# load-cell.net
KiCad netlist of a schematic drawn in EAGLE
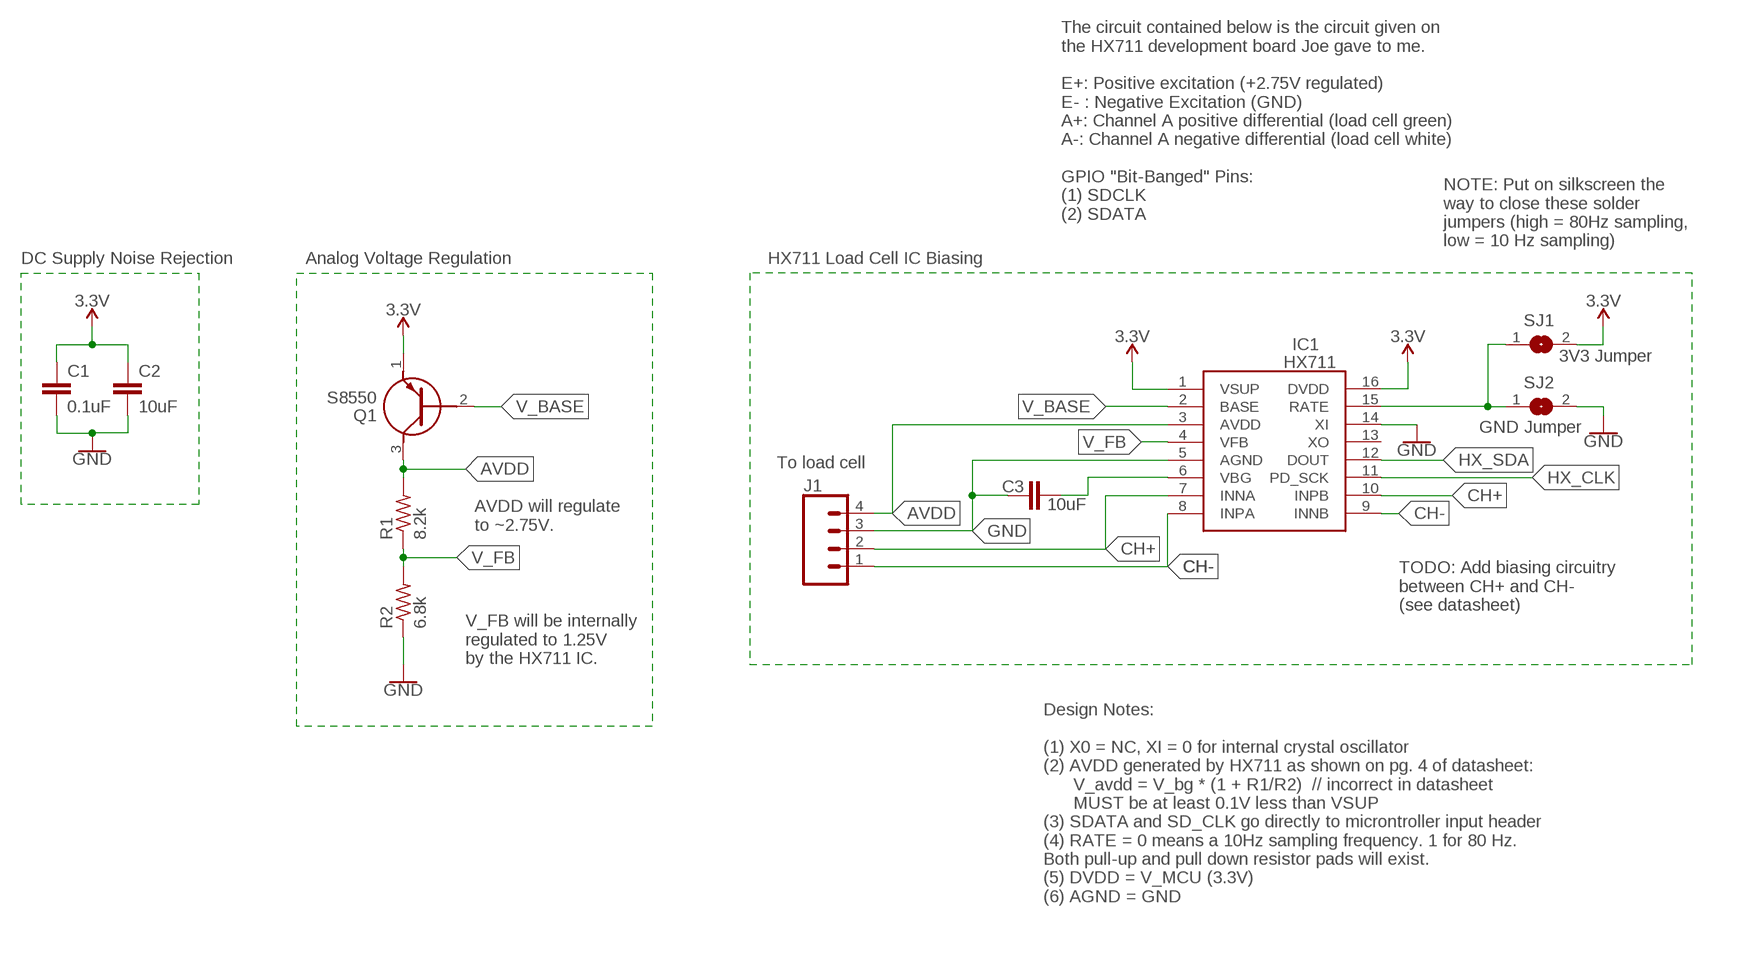
[diagram p0: schematic, sheet 1]

(export (version "E")
  (design (tool "Eeschema 10.0.6"))
  (components
    (comp (ref "C1")
      (value "0.1uF")
      (footprint "eagle-import:C0603")
      (libsource (lib "eagle-import") (part "CAPACITOR0603"))
    )
    (comp (ref "C2")
      (value "10uF")
      (footprint "eagle-import:C0603")
      (libsource (lib "eagle-import") (part "CAPACITOR0603"))
    )
    (comp (ref "C3")
      (value "10uF")
      (footprint "eagle-import:C0603")
      (libsource (lib "eagle-import") (part "CAPACITOR0603"))
    )
    (comp (ref "IC1")
      (value "HX711")
      (footprint "eagle-import:SOIC127P600X160-16N")
      (libsource (lib "eagle-import") (part "HX711"))
    )
    (comp (ref "J1")
      (value "CONN_04")
      (footprint "eagle-import:1X04")
      (libsource (lib "eagle-import") (part "CONN_04"))
    )
    (comp (ref "Q1")
      (value "S8550")
      (footprint "eagle-import:MJE13001TP")
      (libsource (lib "eagle-import") (part "S8550"))
    )
    (comp (ref "R1")
      (value "8.2k")
      (footprint "eagle-import:R0603")
      (libsource (lib "eagle-import") (part "RESISTOR0603"))
    )
    (comp (ref "R2")
      (value "6.8k")
      (footprint "eagle-import:R0603")
      (libsource (lib "eagle-import") (part "RESISTOR0603"))
    )
    (comp (ref "SJ1")
      (value "3V3 Jumper")
      (footprint "eagle-import:SJ")
      (libsource (lib "eagle-import") (part "SJ"))
    )
    (comp (ref "SJ2")
      (value "GND Jumper")
      (footprint "eagle-import:SJ")
      (libsource (lib "eagle-import") (part "SJ"))
    )
  )
  (nets
    (net (code "1") (name "3.3V") (class "Default")
      (node (ref "C1") (pin "1") (pinfunction "1_1") (pintype "passive"))
      (node (ref "C2") (pin "1") (pinfunction "1_1") (pintype "passive"))
      (node (ref "IC1") (pin "1") (pinfunction "VSUP_1") (pintype "bidirectional"))
      (node (ref "IC1") (pin "16") (pinfunction "DVDD_16") (pintype "bidirectional"))
      (node (ref "Q1") (pin "1") (pinfunction "E_1") (pintype "bidirectional"))
      (node (ref "SJ1") (pin "2") (pinfunction "2_2") (pintype "passive"))
    )
    (net (code "2") (name "AVDD") (class "Default")
      (node (ref "IC1") (pin "3") (pinfunction "AVDD_3") (pintype "bidirectional"))
      (node (ref "J1") (pin "4") (pinfunction "4_4") (pintype "passive"))
      (node (ref "Q1") (pin "3") (pinfunction "C_3") (pintype "bidirectional"))
      (node (ref "R1") (pin "2") (pinfunction "2_2") (pintype "passive"))
    )
    (net (code "3") (name "CH+") (class "Default")
      (node (ref "IC1") (pin "10") (pinfunction "INPB_10") (pintype "bidirectional"))
      (node (ref "IC1") (pin "7") (pinfunction "INNA_7") (pintype "bidirectional"))
      (node (ref "J1") (pin "2") (pinfunction "2_2") (pintype "passive"))
    )
    (net (code "4") (name "CH-") (class "Default")
      (node (ref "IC1") (pin "8") (pinfunction "INPA_8") (pintype "bidirectional"))
      (node (ref "IC1") (pin "9") (pinfunction "INNB_9") (pintype "bidirectional"))
      (node (ref "J1") (pin "1") (pinfunction "1_1") (pintype "passive"))
    )
    (net (code "5") (name "GND") (class "Default")
      (node (ref "C1") (pin "2") (pinfunction "2_2") (pintype "passive"))
      (node (ref "C2") (pin "2") (pinfunction "2_2") (pintype "passive"))
      (node (ref "C3") (pin "1") (pinfunction "1_1") (pintype "passive"))
      (node (ref "IC1") (pin "14") (pinfunction "XI_14") (pintype "bidirectional"))
      (node (ref "IC1") (pin "5") (pinfunction "AGND_5") (pintype "bidirectional"))
      (node (ref "J1") (pin "3") (pinfunction "3_3") (pintype "passive"))
      (node (ref "R2") (pin "1") (pinfunction "1_1") (pintype "passive"))
      (node (ref "SJ2") (pin "2") (pinfunction "2_2") (pintype "passive"))
    )
    (net (code "6") (name "HX_CLK") (class "Default")
      (node (ref "IC1") (pin "11") (pinfunction "PD_SCK_11") (pintype "bidirectional"))
    )
    (net (code "7") (name "HX_SDA") (class "Default")
      (node (ref "IC1") (pin "12") (pinfunction "DOUT_12") (pintype "bidirectional"))
    )
    (net (code "8") (name "Net-(IC1-RATE)") (class "Default")
      (node (ref "IC1") (pin "15") (pinfunction "RATE_15") (pintype "bidirectional"))
      (node (ref "SJ1") (pin "1") (pinfunction "1_1") (pintype "passive"))
      (node (ref "SJ2") (pin "1") (pinfunction "1_1") (pintype "passive"))
    )
    (net (code "9") (name "Net-(IC1-VBG)") (class "Default")
      (node (ref "C3") (pin "2") (pinfunction "2_2") (pintype "passive"))
      (node (ref "IC1") (pin "6") (pinfunction "VBG_6") (pintype "bidirectional"))
    )
    (net (code "10") (name "V_BASE") (class "Default")
      (node (ref "IC1") (pin "2") (pinfunction "BASE_2") (pintype "bidirectional"))
      (node (ref "Q1") (pin "2") (pinfunction "B_2") (pintype "bidirectional"))
    )
    (net (code "11") (name "V_FB") (class "Default")
      (node (ref "IC1") (pin "4") (pinfunction "VFB_4") (pintype "bidirectional"))
      (node (ref "R1") (pin "1") (pinfunction "1_1") (pintype "passive"))
      (node (ref "R2") (pin "2") (pinfunction "2_2") (pintype "passive"))
    )
    (net (code "12") (name "unconnected-(IC1-XO-Pad13)") (class "Default")
      (node (ref "IC1") (pin "13") (pinfunction "XO_13") (pintype "bidirectional"))
    )
  )
)
